# MultiChannelLdc4.net
KiCad netlist of a schematic drawn in Altium Designer
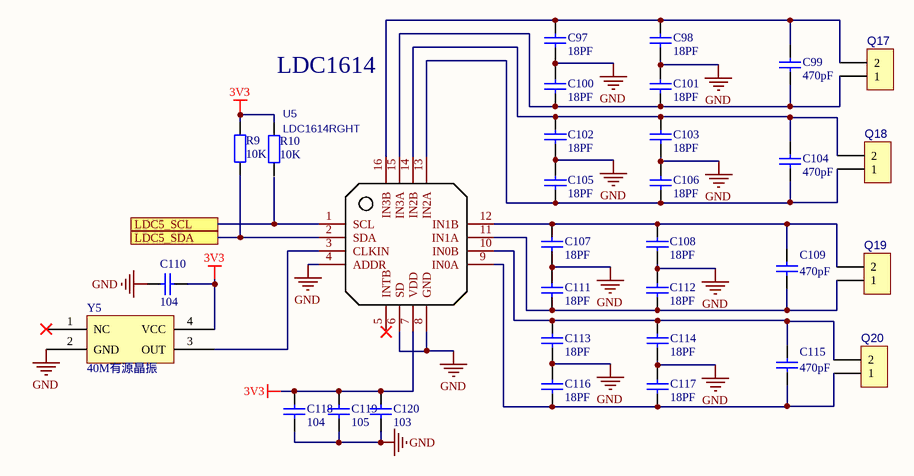
[diagram p0: MultiChannelLdc4.SchDoc]

(export (version "E")
  (design (tool "Eeschema 10.0.6"))
  (components
    (comp (ref "C97")
      (value "18PF")
      (footprint "C0603_L")
      (description "Capacitor")
      (fields (field (name "PUBLISHER") "Altium Limited"))
      (libsource (lib "STM32F103C8T6") (part "Cap"))
    )
    (comp (ref "C98")
      (value "18PF")
      (footprint "C0603_L")
      (description "Capacitor")
      (fields (field (name "PUBLISHER") "Altium Limited"))
      (libsource (lib "STM32F103C8T6") (part "Cap"))
    )
    (comp (ref "C99")
      (value "470pF")
      (footprint "C0603_L")
      (description "Capacitor")
      (fields (field (name "PUBLISHER") "Altium Limited"))
      (libsource (lib "STM32F103C8T6") (part "Cap"))
    )
    (comp (ref "C100")
      (value "18PF")
      (footprint "C0603_L")
      (description "Capacitor")
      (fields (field (name "PUBLISHER") "Altium Limited"))
      (libsource (lib "STM32F103C8T6") (part "Cap"))
    )
    (comp (ref "C101")
      (value "18PF")
      (footprint "C0603_L")
      (description "Capacitor")
      (fields (field (name "PUBLISHER") "Altium Limited"))
      (libsource (lib "STM32F103C8T6") (part "Cap"))
    )
    (comp (ref "C102")
      (value "18PF")
      (footprint "C0603_L")
      (description "Capacitor")
      (fields (field (name "PUBLISHER") "Altium Limited"))
      (libsource (lib "STM32F103C8T6") (part "Cap"))
    )
    (comp (ref "C103")
      (value "18PF")
      (footprint "C0603_L")
      (description "Capacitor")
      (fields (field (name "PUBLISHER") "Altium Limited"))
      (libsource (lib "STM32F103C8T6") (part "Cap"))
    )
    (comp (ref "C104")
      (value "470pF")
      (footprint "C0603_L")
      (description "Capacitor")
      (fields (field (name "PUBLISHER") "Altium Limited"))
      (libsource (lib "STM32F103C8T6") (part "Cap"))
    )
    (comp (ref "C105")
      (value "18PF")
      (footprint "C0603_L")
      (description "Capacitor")
      (fields (field (name "PUBLISHER") "Altium Limited"))
      (libsource (lib "STM32F103C8T6") (part "Cap"))
    )
    (comp (ref "C106")
      (value "18PF")
      (footprint "C0603_L")
      (description "Capacitor")
      (fields (field (name "PUBLISHER") "Altium Limited"))
      (libsource (lib "STM32F103C8T6") (part "Cap"))
    )
    (comp (ref "C107")
      (value "18PF")
      (footprint "C0603_L")
      (description "Capacitor")
      (fields (field (name "PUBLISHER") "Altium Limited"))
      (libsource (lib "STM32F103C8T6") (part "Cap"))
    )
    (comp (ref "C108")
      (value "18PF")
      (footprint "C0603_L")
      (description "Capacitor")
      (fields (field (name "PUBLISHER") "Altium Limited"))
      (libsource (lib "STM32F103C8T6") (part "Cap"))
    )
    (comp (ref "C109")
      (value "470pF")
      (footprint "C0603_L")
      (description "Capacitor")
      (fields (field (name "PUBLISHER") "Altium Limited"))
      (libsource (lib "STM32F103C8T6") (part "Cap"))
    )
    (comp (ref "C110")
      (value "104")
      (footprint "C0603_L")
      (description "贴片电容/MLCC电容")
      (libsource (lib "Ldc1614_Pro") (part "C"))
    )
    (comp (ref "C111")
      (value "18PF")
      (footprint "C0603_L")
      (description "Capacitor")
      (fields (field (name "PUBLISHER") "Altium Limited"))
      (libsource (lib "STM32F103C8T6") (part "Cap"))
    )
    (comp (ref "C112")
      (value "18PF")
      (footprint "C0603_L")
      (description "Capacitor")
      (fields (field (name "PUBLISHER") "Altium Limited"))
      (libsource (lib "STM32F103C8T6") (part "Cap"))
    )
    (comp (ref "C113")
      (value "18PF")
      (footprint "C0603_L")
      (description "Capacitor")
      (fields (field (name "PUBLISHER") "Altium Limited"))
      (libsource (lib "STM32F103C8T6") (part "Cap"))
    )
    (comp (ref "C114")
      (value "18PF")
      (footprint "C0603_L")
      (description "Capacitor")
      (fields (field (name "PUBLISHER") "Altium Limited"))
      (libsource (lib "STM32F103C8T6") (part "Cap"))
    )
    (comp (ref "C115")
      (value "470pF")
      (footprint "C0603_L")
      (description "Capacitor")
      (fields (field (name "PUBLISHER") "Altium Limited"))
      (libsource (lib "STM32F103C8T6") (part "Cap"))
    )
    (comp (ref "C116")
      (value "18PF")
      (footprint "C0603_L")
      (description "Capacitor")
      (fields (field (name "PUBLISHER") "Altium Limited"))
      (libsource (lib "STM32F103C8T6") (part "Cap"))
    )
    (comp (ref "C117")
      (value "18PF")
      (footprint "C0603_L")
      (description "Capacitor")
      (fields (field (name "PUBLISHER") "Altium Limited"))
      (libsource (lib "STM32F103C8T6") (part "Cap"))
    )
    (comp (ref "C118")
      (value "104")
      (footprint "C0603_L")
      (description "Capacitor")
      (fields (field (name "PUBLISHER") "Altium Limited"))
      (libsource (lib "STM32F103C8T6") (part "Cap"))
    )
    (comp (ref "C119")
      (value "105")
      (footprint "C0603_L")
      (description "Capacitor")
      (fields (field (name "PUBLISHER") "Altium Limited"))
      (libsource (lib "STM32F103C8T6") (part "Cap"))
    )
    (comp (ref "C120")
      (value "103")
      (footprint "C0603_L")
      (description "Capacitor")
      (fields (field (name "PUBLISHER") "Altium Limited"))
      (libsource (lib "STM32F103C8T6") (part "Cap"))
    )
    (comp (ref "Q17")
      (value "~")
      (footprint "座子")
      (description "Connector")
      (libsource (lib "*") (part "CON2"))
    )
    (comp (ref "Q18")
      (value "~")
      (footprint "座子")
      (description "Connector")
      (libsource (lib "*") (part "CON2"))
    )
    (comp (ref "Q19")
      (value "~")
      (footprint "座子")
      (description "Connector")
      (libsource (lib "*") (part "CON2"))
    )
    (comp (ref "Q20")
      (value "~")
      (footprint "座子")
      (description "Connector")
      (libsource (lib "*") (part "CON2"))
    )
    (comp (ref "R9")
      (value "10K")
      (footprint "R0603_L")
      (description "Resistor")
      (fields (field (name "Comment") "Res2") (field (name "PUBLISHER") "Altium Limited"))
      (libsource (lib "LDC") (part "Res2"))
    )
    (comp (ref "R10")
      (value "10K")
      (footprint "R0603_L")
      (description "Resistor")
      (fields (field (name "Comment") "Res2") (field (name "PUBLISHER") "Altium Limited"))
      (libsource (lib "Miscellaneous Devices") (part "Res2"))
    )
    (comp (ref "U5")
      (value "LDC1614RGHT")
      (footprint "W-QFN-16")
      (fields
        (field (name "BOM_MANUFACTURER PART") "LDC1314RGHT")
        (field (name "BOM_SUPPLIER PART") "C80399")
      )
      (libsource (lib "LDC1614") (part "LDC1614RGHT"))
    )
    (comp (ref "Y5") (value "40M有源晶振") (footprint "SMD3225") (libsource (lib "其他常用元件类") (part "有源晶振")))
  )
  (nets
    (net (code "1") (name "/LDC5_SCL") (class "Default")
      (node (ref "U5") (pin "1") (pinfunction "SCL_1") (pintype "passive"))
    )
    (net (code "2") (name "/LDC5_SDA") (class "Default")
      (node (ref "R9") (pin "1") (pinfunction "1_1") (pintype "passive"))
      (node (ref "U5") (pin "2") (pinfunction "SDA_2") (pintype "passive"))
    )
    (net (code "3") (name "3V3") (class "Default")
      (node (ref "C110") (pin "1") (pinfunction "1_1") (pintype "passive"))
      (node (ref "C118") (pin "1") (pinfunction "1_1") (pintype "passive"))
      (node (ref "C119") (pin "1") (pinfunction "1_1") (pintype "passive"))
      (node (ref "C120") (pin "1") (pinfunction "1_1") (pintype "passive"))
      (node (ref "R10") (pin "1") (pinfunction "1_1") (pintype "passive"))
      (node (ref "R9") (pin "2") (pinfunction "2_2") (pintype "passive"))
      (node (ref "U5") (pin "7") (pinfunction "VDD_7") (pintype "passive"))
      (node (ref "Y5") (pin "4") (pinfunction "VCC_4") (pintype "passive"))
    )
    (net (code "4") (name "GND") (class "Default")
      (node (ref "C100") (pin "1") (pinfunction "1_1") (pintype "passive"))
      (node (ref "C101") (pin "1") (pinfunction "1_1") (pintype "passive"))
      (node (ref "C102") (pin "2") (pinfunction "2_2") (pintype "passive"))
      (node (ref "C103") (pin "2") (pinfunction "2_2") (pintype "passive"))
      (node (ref "C105") (pin "1") (pinfunction "1_1") (pintype "passive"))
      (node (ref "C106") (pin "1") (pinfunction "1_1") (pintype "passive"))
      (node (ref "C107") (pin "2") (pinfunction "2_2") (pintype "passive"))
      (node (ref "C108") (pin "2") (pinfunction "2_2") (pintype "passive"))
      (node (ref "C110") (pin "2") (pinfunction "2_2") (pintype "passive"))
      (node (ref "C111") (pin "1") (pinfunction "1_1") (pintype "passive"))
      (node (ref "C112") (pin "1") (pinfunction "1_1") (pintype "passive"))
      (node (ref "C113") (pin "2") (pinfunction "2_2") (pintype "passive"))
      (node (ref "C114") (pin "2") (pinfunction "2_2") (pintype "passive"))
      (node (ref "C116") (pin "1") (pinfunction "1_1") (pintype "passive"))
      (node (ref "C117") (pin "1") (pinfunction "1_1") (pintype "passive"))
      (node (ref "C118") (pin "2") (pinfunction "2_2") (pintype "passive"))
      (node (ref "C119") (pin "2") (pinfunction "2_2") (pintype "passive"))
      (node (ref "C120") (pin "2") (pinfunction "2_2") (pintype "passive"))
      (node (ref "C97") (pin "2") (pinfunction "2_2") (pintype "passive"))
      (node (ref "C98") (pin "2") (pinfunction "2_2") (pintype "passive"))
      (node (ref "U5") (pin "4") (pinfunction "ADDR_4") (pintype "passive"))
      (node (ref "U5") (pin "6") (pinfunction "SD_6") (pintype "passive"))
      (node (ref "U5") (pin "8") (pinfunction "GND_8") (pintype "passive"))
      (node (ref "Y5") (pin "2") (pinfunction "GND_2") (pintype "passive"))
    )
    (net (code "5") (name "Net-(U5-CLKIN)") (class "Default")
      (node (ref "U5") (pin "3") (pinfunction "CLKIN_3") (pintype "passive"))
      (node (ref "Y5") (pin "3") (pinfunction "OUT_3") (pintype "passive"))
    )
    (net (code "6") (name "Net-(U5-IN0A)") (class "Default")
      (node (ref "C115") (pin "1") (pinfunction "1_1") (pintype "passive"))
      (node (ref "C116") (pin "2") (pinfunction "2_2") (pintype "passive"))
      (node (ref "C117") (pin "2") (pinfunction "2_2") (pintype "passive"))
      (node (ref "Q20") (pin "1") (pinfunction "1_1") (pintype "passive"))
      (node (ref "U5") (pin "9") (pinfunction "IN0A_9") (pintype "passive"))
    )
    (net (code "7") (name "Net-(U5-IN0B)") (class "Default")
      (node (ref "C113") (pin "1") (pinfunction "1_1") (pintype "passive"))
      (node (ref "C114") (pin "1") (pinfunction "1_1") (pintype "passive"))
      (node (ref "C115") (pin "2") (pinfunction "2_2") (pintype "passive"))
      (node (ref "Q20") (pin "2") (pinfunction "2_2") (pintype "passive"))
      (node (ref "U5") (pin "10") (pinfunction "IN0B_10") (pintype "passive"))
    )
    (net (code "8") (name "Net-(U5-IN1A)") (class "Default")
      (node (ref "C109") (pin "1") (pinfunction "1_1") (pintype "passive"))
      (node (ref "C111") (pin "2") (pinfunction "2_2") (pintype "passive"))
      (node (ref "C112") (pin "2") (pinfunction "2_2") (pintype "passive"))
      (node (ref "Q19") (pin "1") (pinfunction "1_1") (pintype "passive"))
      (node (ref "U5") (pin "11") (pinfunction "IN1A_11") (pintype "passive"))
    )
    (net (code "9") (name "Net-(U5-IN1B)") (class "Default")
      (node (ref "C107") (pin "1") (pinfunction "1_1") (pintype "passive"))
      (node (ref "C108") (pin "1") (pinfunction "1_1") (pintype "passive"))
      (node (ref "C109") (pin "2") (pinfunction "2_2") (pintype "passive"))
      (node (ref "Q19") (pin "2") (pinfunction "2_2") (pintype "passive"))
      (node (ref "U5") (pin "12") (pinfunction "IN1B_12") (pintype "passive"))
    )
    (net (code "10") (name "Net-(U5-IN2A)") (class "Default")
      (node (ref "C104") (pin "1") (pinfunction "1_1") (pintype "passive"))
      (node (ref "C105") (pin "2") (pinfunction "2_2") (pintype "passive"))
      (node (ref "C106") (pin "2") (pinfunction "2_2") (pintype "passive"))
      (node (ref "Q18") (pin "1") (pinfunction "1_1") (pintype "passive"))
      (node (ref "U5") (pin "13") (pinfunction "IN2A_13") (pintype "passive"))
    )
    (net (code "11") (name "Net-(U5-IN2B)") (class "Default")
      (node (ref "C102") (pin "1") (pinfunction "1_1") (pintype "passive"))
      (node (ref "C103") (pin "1") (pinfunction "1_1") (pintype "passive"))
      (node (ref "C104") (pin "2") (pinfunction "2_2") (pintype "passive"))
      (node (ref "Q18") (pin "2") (pinfunction "2_2") (pintype "passive"))
      (node (ref "U5") (pin "14") (pinfunction "IN2B_14") (pintype "passive"))
    )
    (net (code "12") (name "Net-(U5-IN3A)") (class "Default")
      (node (ref "C100") (pin "2") (pinfunction "2_2") (pintype "passive"))
      (node (ref "C101") (pin "2") (pinfunction "2_2") (pintype "passive"))
      (node (ref "C99") (pin "1") (pinfunction "1_1") (pintype "passive"))
      (node (ref "Q17") (pin "1") (pinfunction "1_1") (pintype "passive"))
      (node (ref "U5") (pin "15") (pinfunction "IN3A_15") (pintype "passive"))
    )
    (net (code "13") (name "Net-(U5-IN3B)") (class "Default")
      (node (ref "C97") (pin "1") (pinfunction "1_1") (pintype "passive"))
      (node (ref "C98") (pin "1") (pinfunction "1_1") (pintype "passive"))
      (node (ref "C99") (pin "2") (pinfunction "2_2") (pintype "passive"))
      (node (ref "Q17") (pin "2") (pinfunction "2_2") (pintype "passive"))
      (node (ref "U5") (pin "16") (pinfunction "IN3B_16") (pintype "passive"))
    )
    (net (code "14") (name "unconnected-(R10-Pad2)") (class "Default")
      (node (ref "R10") (pin "2") (pinfunction "2_2") (pintype "passive"))
    )
    (net (code "15") (name "unconnected-(U5-INTB-Pad5)") (class "Default")
      (node (ref "U5") (pin "5") (pinfunction "INTB_5") (pintype "passive+no_connect"))
    )
    (net (code "16") (name "unconnected-(Y5-NC-Pad1)") (class "Default")
      (node (ref "Y5") (pin "1") (pinfunction "NC_1") (pintype "passive+no_connect"))
    )
  )
)
